# AudioPower.net
KiCad netlist of a schematic drawn in EasyEDA Pro
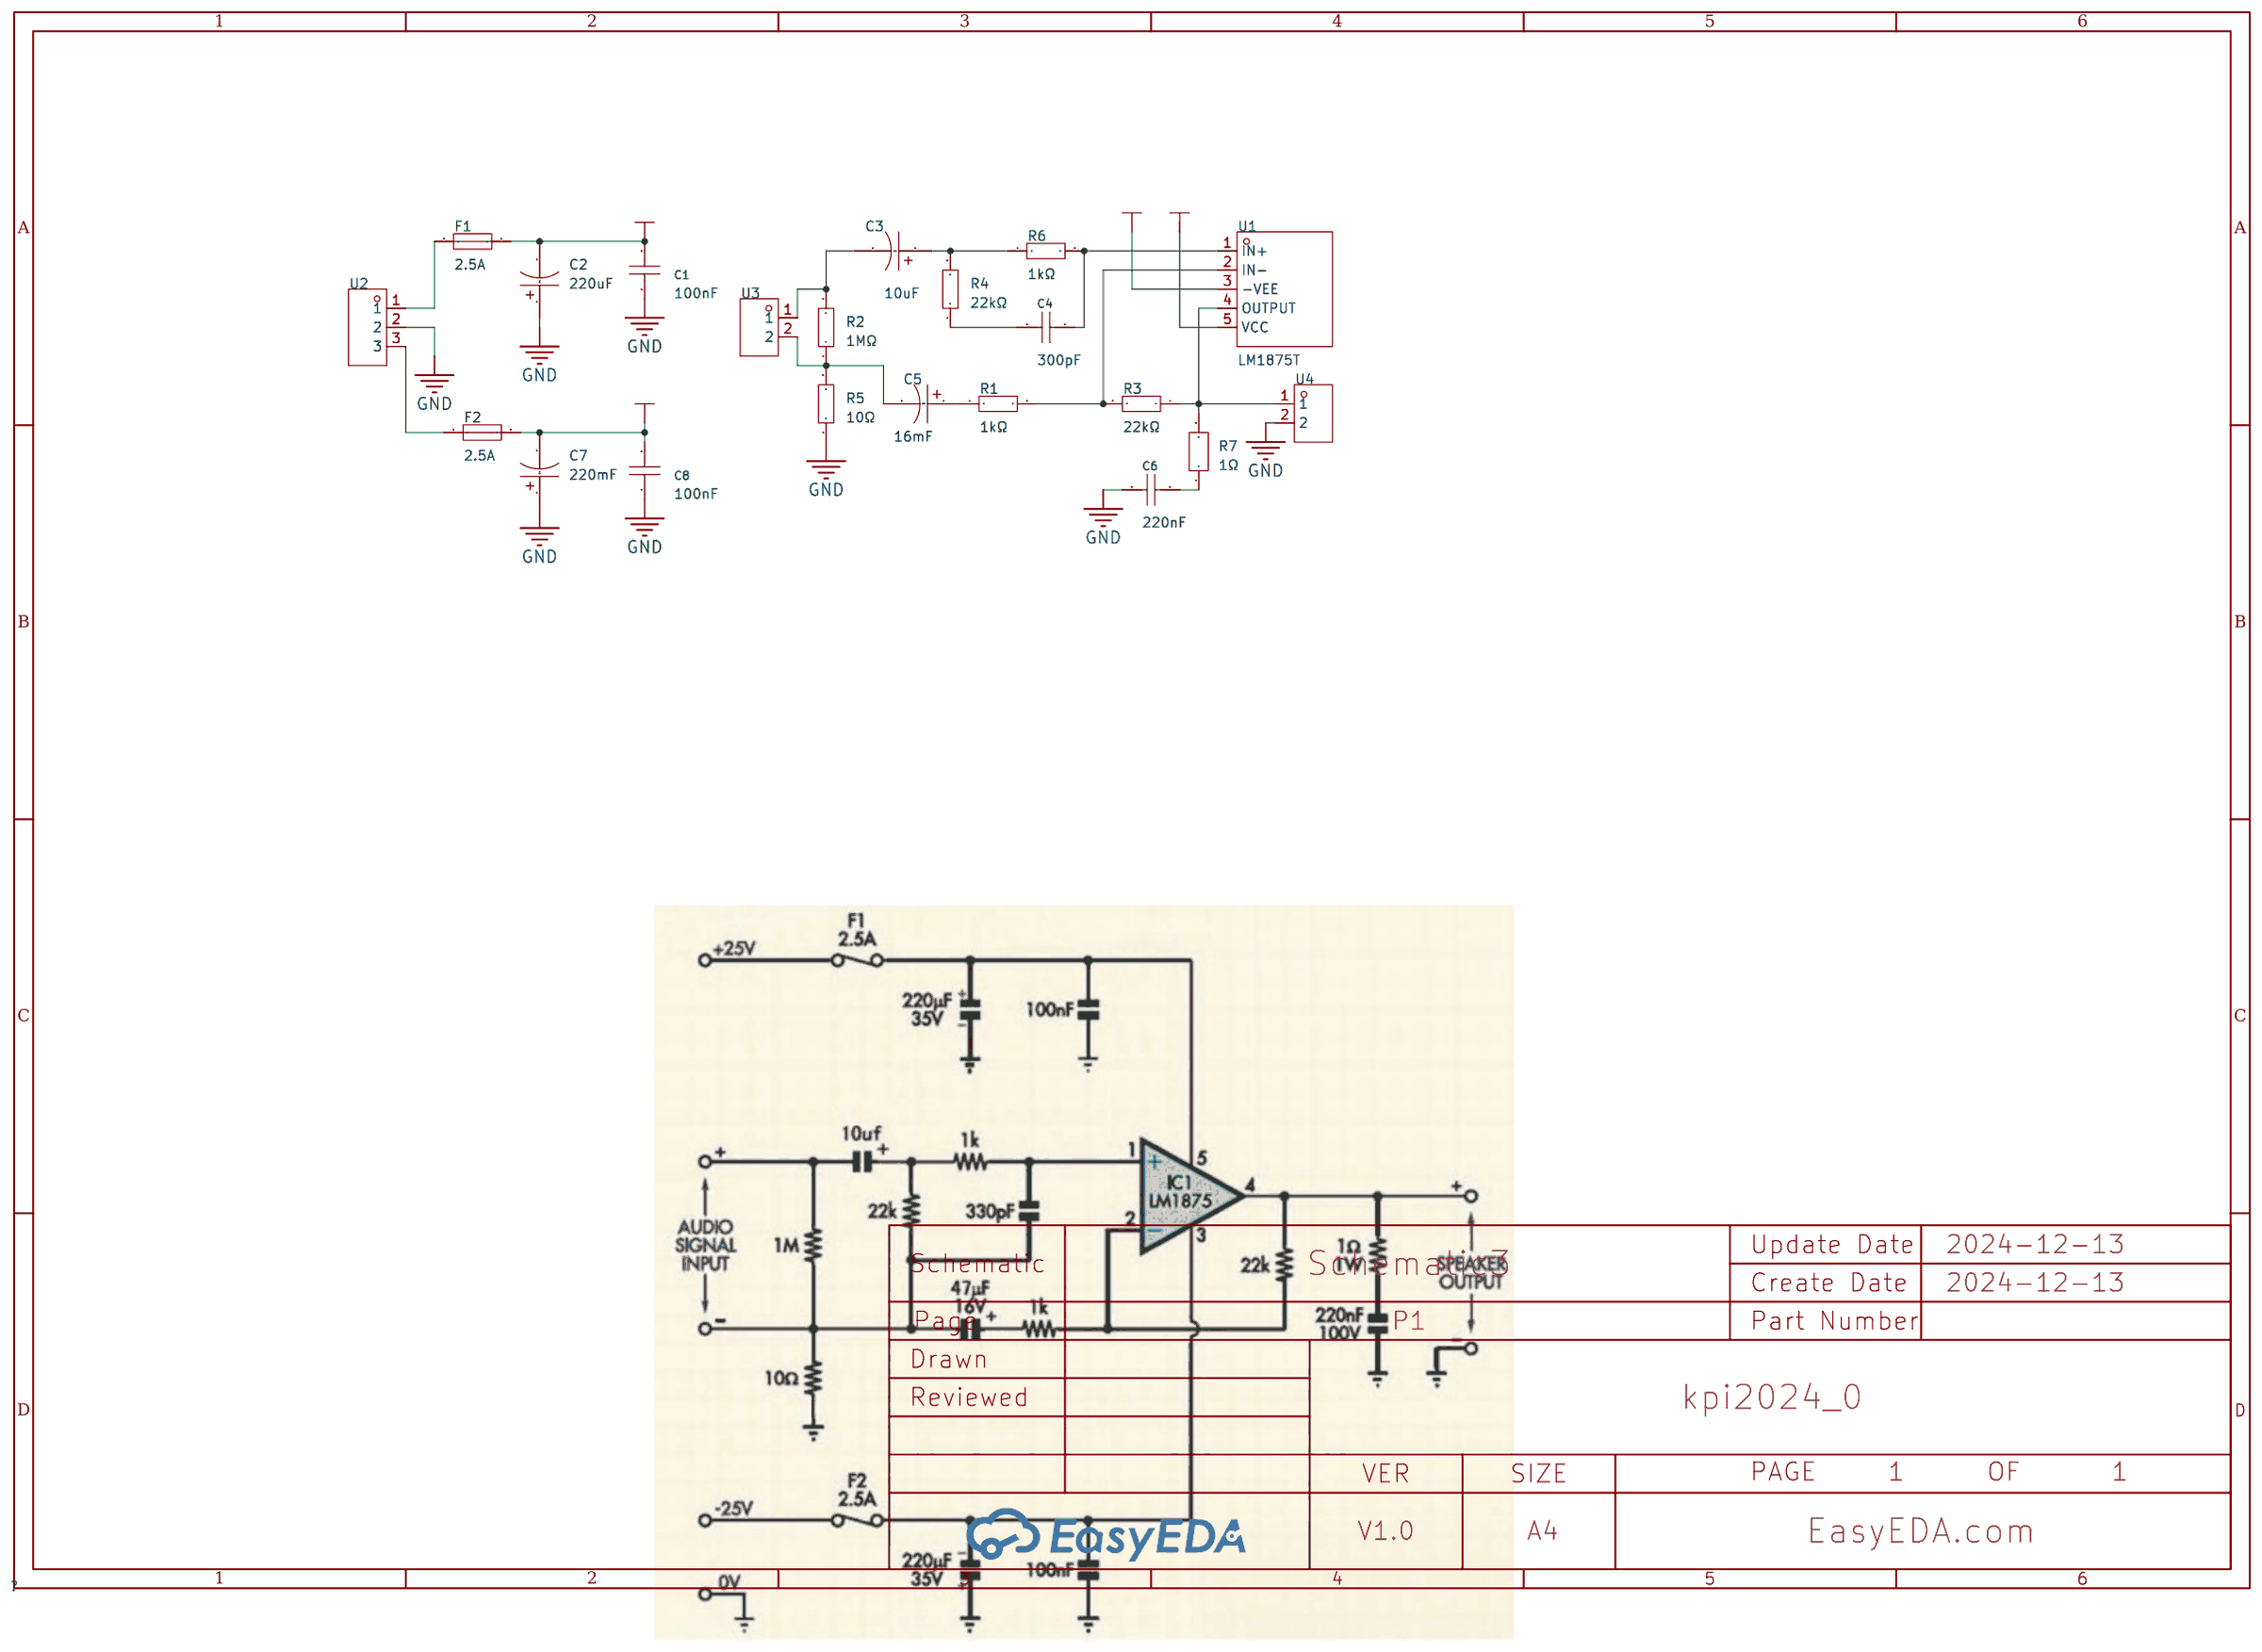
[diagram p0: schematic sheet]

(export (version "E")
  (design (tool "Eeschema 10.0.6"))
  (components
    (comp (ref "C1")
      (value "100nF")
      (footprint "easyedapro:C0603")
      (fields (field (name "Manufacturer Part") "0603B104K500NT") (field (name "Manufacturer") "FH(风华)"))
      (libsource (lib "easyedapro") (part "0603B104K500NT"))
    )
    (comp (ref "C2")
      (value "220uF")
      (footprint "easyedapro:CAP-SMD_L7.3-W4.3-FD")
      (fields (field (name "Manufacturer Part") "6TPF220MFL") (field (name "Manufacturer") "PANASONIC(松下)"))
      (libsource (lib "easyedapro") (part "6TPF220MFL"))
    )
    (comp (ref "C3")
      (value "10uF")
      (footprint "easyedapro:CAP-SMD_L7.3-W4.3-FD")
      (fields (field (name "Manufacturer Part") "6TPF220MFL") (field (name "Manufacturer") "PANASONIC(松下)"))
      (libsource (lib "easyedapro") (part "6TPF220MFL"))
    )
    (comp (ref "C4")
      (value "300pF")
      (footprint "easyedapro:C0603")
      (fields (field (name "Manufacturer Part") "0603B104K500NT") (field (name "Manufacturer") "FH(风华)"))
      (libsource (lib "easyedapro") (part "0603B104K500NT"))
    )
    (comp (ref "C5")
      (value "16mF")
      (footprint "easyedapro:CAP-SMD_L7.3-W4.3-FD")
      (fields (field (name "Manufacturer Part") "6TPF220MFL") (field (name "Manufacturer") "PANASONIC(松下)"))
      (libsource (lib "easyedapro") (part "6TPF220MFL"))
    )
    (comp (ref "C6")
      (value "220nF")
      (footprint "easyedapro:C0603")
      (fields (field (name "Manufacturer Part") "0603B104K500NT") (field (name "Manufacturer") "FH(风华)"))
      (libsource (lib "easyedapro") (part "0603B104K500NT"))
    )
    (comp (ref "C7")
      (value "220mF")
      (footprint "easyedapro:CAP-SMD_L7.3-W4.3-FD")
      (fields (field (name "Manufacturer Part") "6TPF220MFL") (field (name "Manufacturer") "PANASONIC(松下)"))
      (libsource (lib "easyedapro") (part "6TPF220MFL"))
    )
    (comp (ref "C8")
      (value "100nF")
      (footprint "easyedapro:C0603")
      (fields (field (name "Manufacturer Part") "0603B104K500NT") (field (name "Manufacturer") "FH(风华)"))
      (libsource (lib "easyedapro") (part "0603B104K500NT"))
    )
    (comp (ref "F1")
      (value "2.5A")
      (footprint "easyedapro:F0603")
      (description "Type:SMD Fuse Current Rating:2.5A")
      (fields (field (name "Manufacturer") "Reomax(瑞迈)"))
      (libsource (lib "easyedapro") (part "R06.000.2.5"))
    )
    (comp (ref "F2")
      (value "2.5A")
      (footprint "easyedapro:F0603")
      (description "Type:SMD Fuse Current Rating:2.5A")
      (fields (field (name "Manufacturer") "Reomax(瑞迈)"))
      (libsource (lib "easyedapro") (part "R06.000.2.5"))
    )
    (comp (ref "R1")
      (value "1kΩ")
      (footprint "easyedapro:R0603")
      (fields
        (field (name "Manufacturer Part") "0603WAF1001T5E")
        (field (name "Manufacturer") "UNI-ROYAL(厚声)")
      )
      (libsource (lib "easyedapro") (part "0603WAF1001T5E"))
    )
    (comp (ref "R2")
      (value "1МΩ")
      (footprint "easyedapro:R0603")
      (fields
        (field (name "Manufacturer Part") "0603WAF1001T5E")
        (field (name "Manufacturer") "UNI-ROYAL(厚声)")
      )
      (libsource (lib "easyedapro") (part "0603WAF1001T5E"))
    )
    (comp (ref "R3")
      (value "22kΩ")
      (footprint "easyedapro:R0603")
      (fields
        (field (name "Manufacturer Part") "0603WAF1001T5E")
        (field (name "Manufacturer") "UNI-ROYAL(厚声)")
      )
      (libsource (lib "easyedapro") (part "0603WAF1001T5E"))
    )
    (comp (ref "R4")
      (value "22kΩ")
      (footprint "easyedapro:R0603")
      (fields
        (field (name "Manufacturer Part") "0603WAF1001T5E")
        (field (name "Manufacturer") "UNI-ROYAL(厚声)")
      )
      (libsource (lib "easyedapro") (part "0603WAF1001T5E"))
    )
    (comp (ref "R5")
      (value "10Ω")
      (footprint "easyedapro:R0603")
      (fields
        (field (name "Manufacturer Part") "0603WAF1001T5E")
        (field (name "Manufacturer") "UNI-ROYAL(厚声)")
      )
      (libsource (lib "easyedapro") (part "0603WAF1001T5E"))
    )
    (comp (ref "R6")
      (value "1kΩ")
      (footprint "easyedapro:R0603")
      (fields
        (field (name "Manufacturer Part") "0603WAF1001T5E")
        (field (name "Manufacturer") "UNI-ROYAL(厚声)")
      )
      (libsource (lib "easyedapro") (part "0603WAF1001T5E"))
    )
    (comp (ref "R7")
      (value "1Ω")
      (footprint "easyedapro:RES-TH_BD4.5-L11.0-P15.00-D0.7")
      (fields
        (field (name "Manufacturer Part") "RN 1W 13R F T/B A1")
        (field (name "Manufacturer") "Tyohm(幸亚电阻)")
      )
      (libsource (lib "easyedapro") (part "RN 1W 13R F T/B A1"))
    )
    (comp (ref "U1")
      (value "LM1875T")
      (footprint "easyedapro:TO-220-5_L10.2-W4.8-P1.70-TL")
      (fields (field (name "Manufacturer") "TI(德州仪器)"))
      (libsource (lib "easyedapro") (part "LM1875T_C2862102"))
    )
    (comp (ref "U2")
      (value "DB910-6.35-3P-GN-P")
      (footprint "easyedapro:CONN-TH_3P-P6.35_DB910-6.35-3P-GN-P")
      (fields (field (name "Manufacturer") "DORABO(地博电气)"))
      (libsource (lib "easyedapro") (part "DB910-6.35-3P-GN-P"))
    )
    (comp (ref "U3")
      (value "TY500-5.0-02P-14-00AH")
      (footprint "easyedapro:CONN-TH_2P-P5.00_TOPONELEC_TY500-5.0-02P-14-00AH")
      (fields (field (name "Manufacturer") "Toponelec(拓宜)"))
      (libsource (lib "easyedapro") (part "TY500-5.0-02P-14-00AH"))
    )
    (comp (ref "U4")
      (value "TY500-5.0-02P-14-00AH")
      (footprint "easyedapro:CONN-TH_2P-P5.00_TOPONELEC_TY500-5.0-02P-14-00AH")
      (fields (field (name "Manufacturer") "Toponelec(拓宜)"))
      (libsource (lib "easyedapro") (part "TY500-5.0-02P-14-00AH"))
    )
  )
  (nets
    (net (code "1") (name "+25V") (class "Default")
      (node (ref "C1") (pin "1") (pinfunction "1_1") (pintype "input"))
      (node (ref "C2") (pin "2") (pinfunction "2_2") (pintype "unspecified"))
      (node (ref "F1") (pin "2") (pinfunction "2_2") (pintype "unspecified"))
      (node (ref "U1") (pin "5") (pinfunction "VCC_5") (pintype "unspecified"))
    )
    (net (code "2") (name "-25V") (class "Default")
      (node (ref "C7") (pin "2") (pinfunction "2_2") (pintype "unspecified"))
      (node (ref "C8") (pin "2") (pinfunction "2_2") (pintype "input"))
      (node (ref "F2") (pin "2") (pinfunction "2_2") (pintype "unspecified"))
      (node (ref "U1") (pin "3") (pinfunction "-VEE_3") (pintype "unspecified"))
    )
    (net (code "3") (name "GND") (class "Default")
      (node (ref "C1") (pin "2") (pinfunction "2_2") (pintype "input"))
      (node (ref "C2") (pin "1") (pinfunction "1_1") (pintype "unspecified"))
      (node (ref "C6") (pin "2") (pinfunction "2_2") (pintype "input"))
      (node (ref "C7") (pin "1") (pinfunction "1_1") (pintype "unspecified"))
      (node (ref "C8") (pin "1") (pinfunction "1_1") (pintype "input"))
      (node (ref "R5") (pin "1") (pinfunction "1_1") (pintype "input"))
      (node (ref "U2") (pin "2") (pinfunction "2_2") (pintype "unspecified"))
      (node (ref "U4") (pin "2") (pinfunction "2_2") (pintype "unspecified"))
    )
    (net (code "4") (name "Net-(C3-Pad1)") (class "Default")
      (node (ref "C3") (pin "1") (pinfunction "1_1") (pintype "unspecified"))
      (node (ref "R4") (pin "2") (pinfunction "2_2") (pintype "input"))
      (node (ref "R6") (pin "1") (pinfunction "1_1") (pintype "input"))
    )
    (net (code "5") (name "Net-(C3-Pad2)") (class "Default")
      (node (ref "C3") (pin "2") (pinfunction "2_2") (pintype "unspecified"))
      (node (ref "R2") (pin "2") (pinfunction "2_2") (pintype "input"))
      (node (ref "U3") (pin "1") (pinfunction "1_1") (pintype "unspecified"))
    )
    (net (code "6") (name "Net-(C4-Pad1)") (class "Default")
      (node (ref "C4") (pin "1") (pinfunction "1_1") (pintype "input"))
      (node (ref "R4") (pin "1") (pinfunction "1_1") (pintype "input"))
    )
    (net (code "7") (name "Net-(C5-Pad1)") (class "Default")
      (node (ref "C5") (pin "1") (pinfunction "1_1") (pintype "unspecified"))
      (node (ref "R1") (pin "1") (pinfunction "1_1") (pintype "input"))
    )
    (net (code "8") (name "Net-(C5-Pad2)") (class "Default")
      (node (ref "C5") (pin "2") (pinfunction "2_2") (pintype "unspecified"))
      (node (ref "R2") (pin "1") (pinfunction "1_1") (pintype "input"))
      (node (ref "R5") (pin "2") (pinfunction "2_2") (pintype "input"))
      (node (ref "U3") (pin "2") (pinfunction "2_2") (pintype "unspecified"))
    )
    (net (code "9") (name "Net-(C6-Pad1)") (class "Default")
      (node (ref "C6") (pin "1") (pinfunction "1_1") (pintype "input"))
      (node (ref "R7") (pin "1") (pinfunction "1_1") (pintype "unspecified"))
    )
    (net (code "10") (name "Net-(F1-Pad1)") (class "Default")
      (node (ref "F1") (pin "1") (pinfunction "1_1") (pintype "unspecified"))
      (node (ref "U2") (pin "1") (pinfunction "1_1") (pintype "unspecified"))
    )
    (net (code "11") (name "Net-(F2-Pad1)") (class "Default")
      (node (ref "F2") (pin "1") (pinfunction "1_1") (pintype "unspecified"))
      (node (ref "U2") (pin "3") (pinfunction "3_3") (pintype "unspecified"))
    )
    (net (code "12") (name "Net-(U1-IN+)") (class "Default")
      (node (ref "C4") (pin "2") (pinfunction "2_2") (pintype "input"))
      (node (ref "R6") (pin "2") (pinfunction "2_2") (pintype "input"))
      (node (ref "U1") (pin "1") (pinfunction "IN+_1") (pintype "unspecified"))
    )
    (net (code "13") (name "Net-(U1-IN-)") (class "Default")
      (node (ref "R1") (pin "2") (pinfunction "2_2") (pintype "input"))
      (node (ref "R3") (pin "2") (pinfunction "2_2") (pintype "input"))
      (node (ref "U1") (pin "2") (pinfunction "IN-_2") (pintype "unspecified"))
    )
    (net (code "14") (name "Net-(U1-OUTPUT)") (class "Default")
      (node (ref "R3") (pin "1") (pinfunction "1_1") (pintype "input"))
      (node (ref "R7") (pin "2") (pinfunction "2_2") (pintype "unspecified"))
      (node (ref "U1") (pin "4") (pinfunction "OUTPUT_4") (pintype "unspecified"))
      (node (ref "U4") (pin "1") (pinfunction "1_1") (pintype "unspecified"))
    )
  )
)
